# BinaryWatch_v0_5.net
KiCad netlist of a schematic drawn in EAGLE
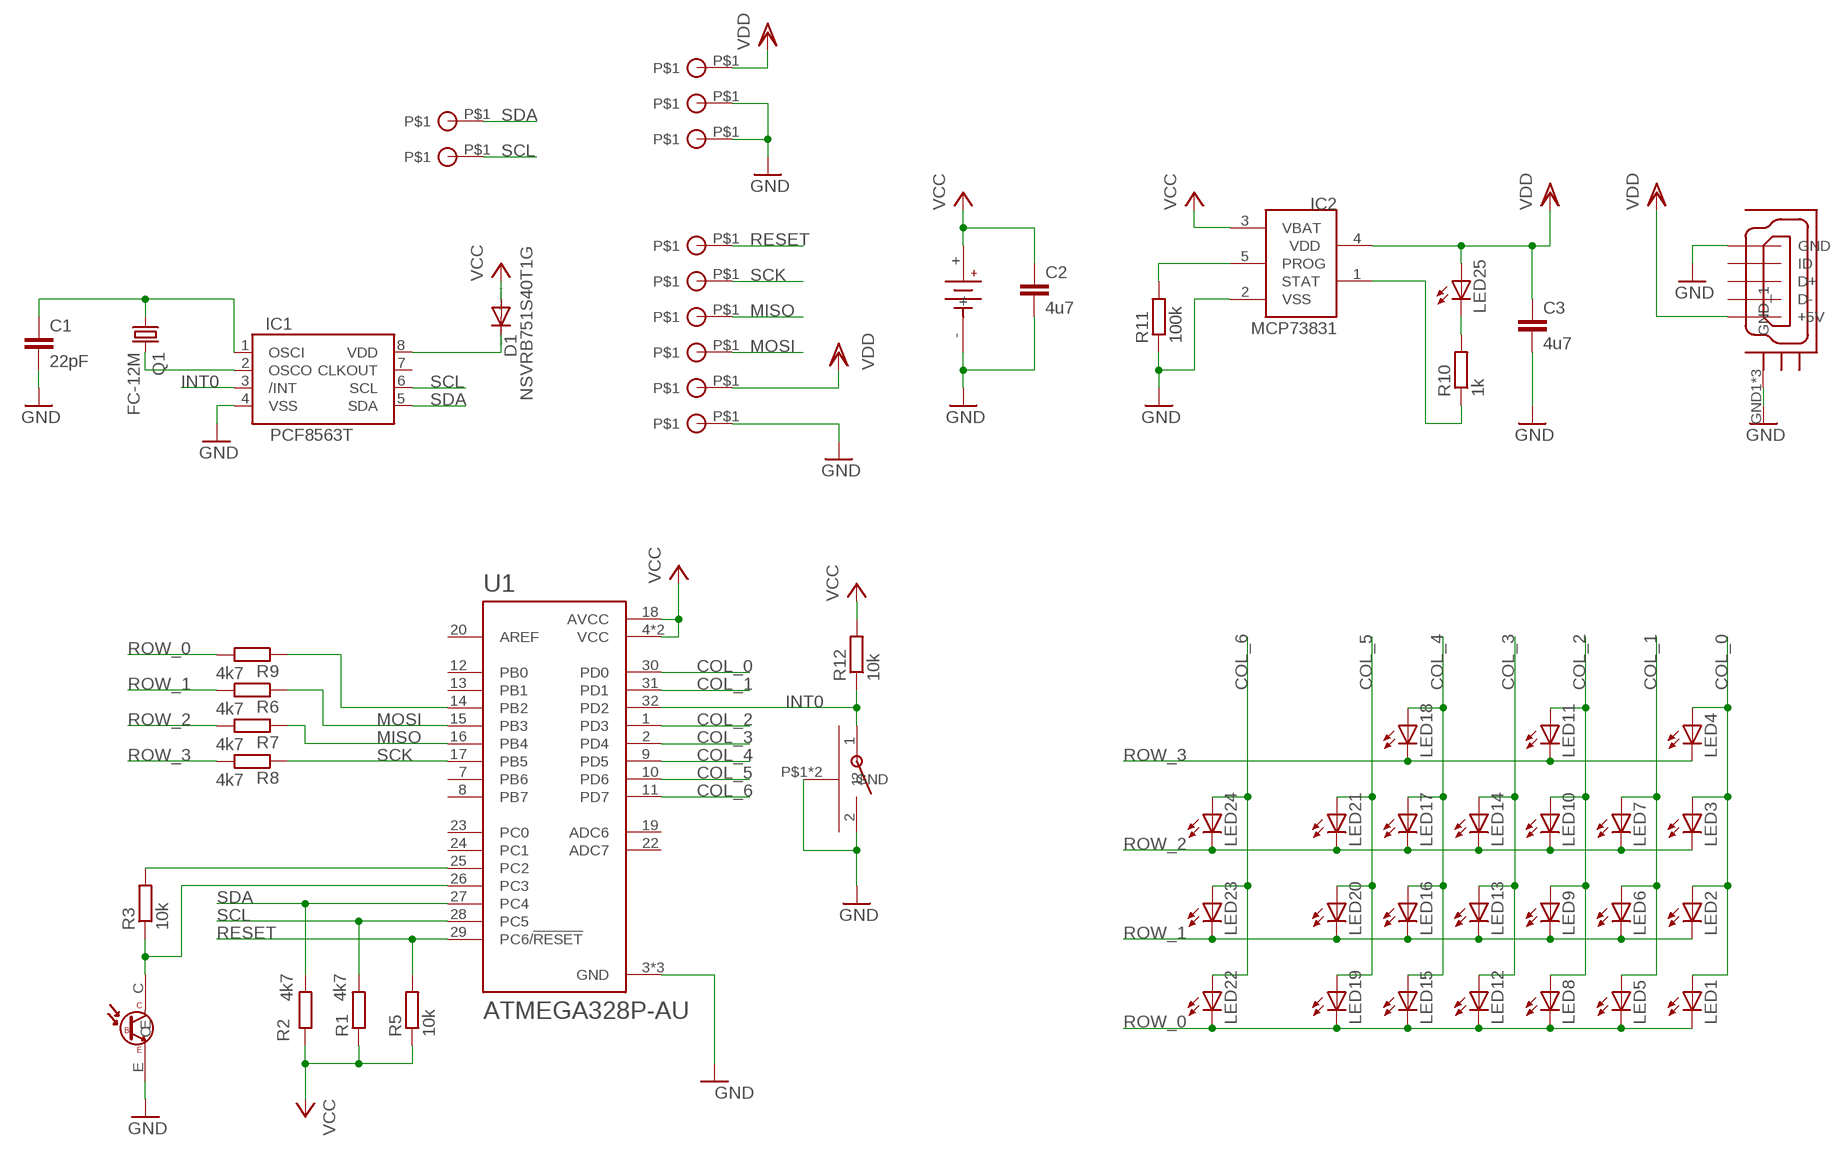
[diagram p0: schematic, sheet 1]

(export (version "E")
  (design (tool "Eeschema 10.0.6"))
  (components
    (comp (ref "C1")
      (value "22pF")
      (footprint "eagle-import:C0603")
      (libsource (lib "eagle-import") (part "C-EUC0603"))
    )
    (comp (ref "C2")
      (value "4u7")
      (footprint "eagle-import:C0603")
      (libsource (lib "eagle-import") (part "C-EUC0603"))
    )
    (comp (ref "C3")
      (value "4u7")
      (footprint "eagle-import:C0603")
      (libsource (lib "eagle-import") (part "C-EUC0603"))
    )
    (comp (ref "D1")
      (value "NSVRB751S40T1G")
      (footprint "eagle-import:SOD523")
      (libsource (lib "eagle-import") (part "DIODE-SOD523"))
    )
    (comp (ref "IC1")
      (value "PCF8563T")
      (footprint "eagle-import:SO8")
      (libsource (lib "eagle-import") (part "PCF8563T"))
    )
    (comp (ref "IC2")
      (value "MCP73831")
      (footprint "eagle-import:SOT23-5L")
      (libsource (lib "eagle-import") (part "MCP73831"))
    )
    (comp (ref "LED1")
      (value "LEDSML0603")
      (footprint "eagle-import:SML0603")
      (libsource (lib "eagle-import") (part "LEDSML0603"))
    )
    (comp (ref "LED2")
      (value "LEDSML0603")
      (footprint "eagle-import:SML0603")
      (libsource (lib "eagle-import") (part "LEDSML0603"))
    )
    (comp (ref "LED3")
      (value "LEDSML0603")
      (footprint "eagle-import:SML0603")
      (libsource (lib "eagle-import") (part "LEDSML0603"))
    )
    (comp (ref "LED4")
      (value "LEDSML0603")
      (footprint "eagle-import:SML0603")
      (libsource (lib "eagle-import") (part "LEDSML0603"))
    )
    (comp (ref "LED5")
      (value "LEDSML0603")
      (footprint "eagle-import:SML0603")
      (libsource (lib "eagle-import") (part "LEDSML0603"))
    )
    (comp (ref "LED6")
      (value "LEDSML0603")
      (footprint "eagle-import:SML0603")
      (libsource (lib "eagle-import") (part "LEDSML0603"))
    )
    (comp (ref "LED7")
      (value "LEDSML0603")
      (footprint "eagle-import:SML0603")
      (libsource (lib "eagle-import") (part "LEDSML0603"))
    )
    (comp (ref "LED8")
      (value "LEDSML0603")
      (footprint "eagle-import:SML0603")
      (libsource (lib "eagle-import") (part "LEDSML0603"))
    )
    (comp (ref "LED9")
      (value "LEDSML0603")
      (footprint "eagle-import:SML0603")
      (libsource (lib "eagle-import") (part "LEDSML0603"))
    )
    (comp (ref "LED10")
      (value "LEDSML0603")
      (footprint "eagle-import:SML0603")
      (libsource (lib "eagle-import") (part "LEDSML0603"))
    )
    (comp (ref "LED11")
      (value "LEDSML0603")
      (footprint "eagle-import:SML0603")
      (libsource (lib "eagle-import") (part "LEDSML0603"))
    )
    (comp (ref "LED12")
      (value "LEDSML0603")
      (footprint "eagle-import:SML0603")
      (libsource (lib "eagle-import") (part "LEDSML0603"))
    )
    (comp (ref "LED13")
      (value "LEDSML0603")
      (footprint "eagle-import:SML0603")
      (libsource (lib "eagle-import") (part "LEDSML0603"))
    )
    (comp (ref "LED14")
      (value "LEDSML0603")
      (footprint "eagle-import:SML0603")
      (libsource (lib "eagle-import") (part "LEDSML0603"))
    )
    (comp (ref "LED15")
      (value "LEDSML0603")
      (footprint "eagle-import:SML0603")
      (libsource (lib "eagle-import") (part "LEDSML0603"))
    )
    (comp (ref "LED16")
      (value "LEDSML0603")
      (footprint "eagle-import:SML0603")
      (libsource (lib "eagle-import") (part "LEDSML0603"))
    )
    (comp (ref "LED17")
      (value "LEDSML0603")
      (footprint "eagle-import:SML0603")
      (libsource (lib "eagle-import") (part "LEDSML0603"))
    )
    (comp (ref "LED18")
      (value "LEDSML0603")
      (footprint "eagle-import:SML0603")
      (libsource (lib "eagle-import") (part "LEDSML0603"))
    )
    (comp (ref "LED19")
      (value "LEDSML0603")
      (footprint "eagle-import:SML0603")
      (libsource (lib "eagle-import") (part "LEDSML0603"))
    )
    (comp (ref "LED20")
      (value "LEDSML0603")
      (footprint "eagle-import:SML0603")
      (libsource (lib "eagle-import") (part "LEDSML0603"))
    )
    (comp (ref "LED21")
      (value "LEDSML0603")
      (footprint "eagle-import:SML0603")
      (libsource (lib "eagle-import") (part "LEDSML0603"))
    )
    (comp (ref "LED22")
      (value "LEDSML0603")
      (footprint "eagle-import:SML0603")
      (libsource (lib "eagle-import") (part "LEDSML0603"))
    )
    (comp (ref "LED23")
      (value "LEDSML0603")
      (footprint "eagle-import:SML0603")
      (libsource (lib "eagle-import") (part "LEDSML0603"))
    )
    (comp (ref "LED24")
      (value "LEDSML0603")
      (footprint "eagle-import:SML0603")
      (libsource (lib "eagle-import") (part "LEDSML0603"))
    )
    (comp (ref "LED25")
      (value "LEDSML0603")
      (footprint "eagle-import:SML0603")
      (libsource (lib "eagle-import") (part "LEDSML0603"))
    )
    (comp (ref "Q1")
      (value "FC-12M")
      (footprint "eagle-import:FC-12M")
      (libsource (lib "eagle-import") (part "FC-12M"))
    )
    (comp (ref "R1")
      (value "4k7")
      (footprint "eagle-import:R0603")
      (libsource (lib "eagle-import") (part "resistor_R-EU_R0603"))
    )
    (comp (ref "R2")
      (value "4k7")
      (footprint "eagle-import:R0603")
      (libsource (lib "eagle-import") (part "resistor_R-EU_R0603"))
    )
    (comp (ref "R3")
      (value "10k")
      (footprint "eagle-import:R0603")
      (libsource (lib "eagle-import") (part "R-EU_R0603"))
    )
    (comp (ref "R5")
      (value "10k")
      (footprint "eagle-import:R0603")
      (libsource (lib "eagle-import") (part "resistor_R-EU_R0603"))
    )
    (comp (ref "R6")
      (value "4k7")
      (footprint "eagle-import:R0603")
      (libsource (lib "eagle-import") (part "resistor_R-EU_R0603"))
    )
    (comp (ref "R7")
      (value "4k7")
      (footprint "eagle-import:R0603")
      (libsource (lib "eagle-import") (part "resistor_R-EU_R0603"))
    )
    (comp (ref "R8")
      (value "4k7")
      (footprint "eagle-import:R0603")
      (libsource (lib "eagle-import") (part "resistor_R-EU_R0603"))
    )
    (comp (ref "R9")
      (value "4k7")
      (footprint "eagle-import:R0603")
      (libsource (lib "eagle-import") (part "resistor_R-EU_R0603"))
    )
    (comp (ref "R10")
      (value "1k")
      (footprint "eagle-import:R0603")
      (libsource (lib "eagle-import") (part "R-EU_R0603"))
    )
    (comp (ref "R11")
      (value "100k")
      (footprint "eagle-import:R0603")
      (libsource (lib "eagle-import") (part "R-EU_R0603"))
    )
    (comp (ref "R12")
      (value "10k")
      (footprint "eagle-import:R0603")
      (libsource (lib "eagle-import") (part "rcl_334_R-EU_R0603"))
    )
    (comp (ref "U$1")
      (value "2032")
      (footprint "eagle-import:2032_45DEG")
      (libsource (lib "eagle-import") (part "2032"))
    )
    (comp (ref "U$2")
      (value "CONTACT_1_8MM")
      (footprint "eagle-import:CONTACT_1_8MM")
      (libsource (lib "eagle-import") (part "CONTACT_1_8MM"))
    )
    (comp (ref "U$3")
      (value "CONTACT_1_8MM")
      (footprint "eagle-import:CONTACT_1_8MM")
      (libsource (lib "eagle-import") (part "CONTACT_1_8MM"))
    )
    (comp (ref "U$4")
      (value "CONTACT_1_8MM")
      (footprint "eagle-import:CONTACT_1_8MM")
      (libsource (lib "eagle-import") (part "CONTACT_1_8MM"))
    )
    (comp (ref "U$5")
      (value "CONTACT_1_8MM")
      (footprint "eagle-import:CONTACT_1_8MM")
      (libsource (lib "eagle-import") (part "CONTACT_1_8MM"))
    )
    (comp (ref "U$6")
      (value "CONTACT_1_8MM")
      (footprint "eagle-import:CONTACT_1_8MM")
      (libsource (lib "eagle-import") (part "CONTACT_1_8MM"))
    )
    (comp (ref "U$7")
      (value "CONTACT_1_8MM")
      (footprint "eagle-import:CONTACT_1_8MM")
      (libsource (lib "eagle-import") (part "CONTACT_1_8MM"))
    )
    (comp (ref "U$8")
      (value "TACK_SWITCH")
      (footprint "eagle-import:TL3330")
      (libsource (lib "eagle-import") (part "TACK_SWITCH"))
    )
    (comp (ref "U$9")
      (value "CONTACT_1_8MM")
      (footprint "eagle-import:CONTACT_1_8MM")
      (libsource (lib "eagle-import") (part "CONTACT_1_8MM"))
    )
    (comp (ref "U$10")
      (value "MICRO_USB_VERTICAL")
      (footprint "eagle-import:MICRO_USB_VERTICAL")
      (libsource (lib "eagle-import") (part "MICRO_USB_VERTICAL"))
    )
    (comp (ref "U$11")
      (value "CONTACT_1_8MM")
      (footprint "eagle-import:CONTACT_1_8MM")
      (libsource (lib "eagle-import") (part "CONTACT_1_8MM"))
    )
    (comp (ref "U$12")
      (value "CONTACT_1_8MM")
      (footprint "eagle-import:CONTACT_1_8MM")
      (libsource (lib "eagle-import") (part "CONTACT_1_8MM"))
    )
    (comp (ref "U$13")
      (value "CONTACT_1_8MM")
      (footprint "eagle-import:CONTACT_1_8MM")
      (libsource (lib "eagle-import") (part "CONTACT_1_8MM"))
    )
    (comp (ref "U$14")
      (value "CONTACT_1_8MM")
      (footprint "eagle-import:CONTACT_1_8MM")
      (libsource (lib "eagle-import") (part "CONTACT_1_8MM"))
    )
    (comp (ref "U$15")
      (value "PHOTOTRANSISTOR_0603")
      (footprint "eagle-import:PHOTO_TRANS_0603")
      (libsource (lib "eagle-import") (part "PHOTOTRANSISTOR_0603"))
    )
    (comp (ref "U1")
      (value "ATMEGA328P-AU")
      (footprint "eagle-import:QFP80P900X900X120-32N")
      (fields (field (name "MF") "Microchip"))
      (libsource (lib "eagle-import") (part "ATMEGA328P-AU"))
    )
  )
  (nets
    (net (code "1") (name "/COL_0") (class "Default")
      (node (ref "LED1") (pin "A") (pinfunction "A_A") (pintype "passive"))
      (node (ref "LED2") (pin "A") (pinfunction "A_A") (pintype "passive"))
      (node (ref "LED3") (pin "A") (pinfunction "A_A") (pintype "passive"))
      (node (ref "LED4") (pin "A") (pinfunction "A_A") (pintype "passive"))
      (node (ref "U1") (pin "30") (pinfunction "PD0_30") (pintype "bidirectional"))
    )
    (net (code "2") (name "/COL_1") (class "Default")
      (node (ref "LED5") (pin "A") (pinfunction "A_A") (pintype "passive"))
      (node (ref "LED6") (pin "A") (pinfunction "A_A") (pintype "passive"))
      (node (ref "LED7") (pin "A") (pinfunction "A_A") (pintype "passive"))
      (node (ref "U1") (pin "31") (pinfunction "PD1_31") (pintype "bidirectional"))
    )
    (net (code "3") (name "/COL_2") (class "Default")
      (node (ref "LED10") (pin "A") (pinfunction "A_A") (pintype "passive"))
      (node (ref "LED11") (pin "A") (pinfunction "A_A") (pintype "passive"))
      (node (ref "LED8") (pin "A") (pinfunction "A_A") (pintype "passive"))
      (node (ref "LED9") (pin "A") (pinfunction "A_A") (pintype "passive"))
      (node (ref "U1") (pin "1") (pinfunction "PD3_1") (pintype "bidirectional"))
    )
    (net (code "4") (name "/COL_3") (class "Default")
      (node (ref "LED12") (pin "A") (pinfunction "A_A") (pintype "passive"))
      (node (ref "LED13") (pin "A") (pinfunction "A_A") (pintype "passive"))
      (node (ref "LED14") (pin "A") (pinfunction "A_A") (pintype "passive"))
      (node (ref "U1") (pin "2") (pinfunction "PD4_2") (pintype "bidirectional"))
    )
    (net (code "5") (name "/COL_4") (class "Default")
      (node (ref "LED15") (pin "A") (pinfunction "A_A") (pintype "passive"))
      (node (ref "LED16") (pin "A") (pinfunction "A_A") (pintype "passive"))
      (node (ref "LED17") (pin "A") (pinfunction "A_A") (pintype "passive"))
      (node (ref "LED18") (pin "A") (pinfunction "A_A") (pintype "passive"))
      (node (ref "U1") (pin "9") (pinfunction "PD5_9") (pintype "bidirectional"))
    )
    (net (code "6") (name "/COL_5") (class "Default")
      (node (ref "LED19") (pin "A") (pinfunction "A_A") (pintype "passive"))
      (node (ref "LED20") (pin "A") (pinfunction "A_A") (pintype "passive"))
      (node (ref "LED21") (pin "A") (pinfunction "A_A") (pintype "passive"))
      (node (ref "U1") (pin "10") (pinfunction "PD6_10") (pintype "bidirectional"))
    )
    (net (code "7") (name "/COL_6") (class "Default")
      (node (ref "LED22") (pin "A") (pinfunction "A_A") (pintype "passive"))
      (node (ref "LED23") (pin "A") (pinfunction "A_A") (pintype "passive"))
      (node (ref "LED24") (pin "A") (pinfunction "A_A") (pintype "passive"))
      (node (ref "U1") (pin "11") (pinfunction "PD7_11") (pintype "bidirectional"))
    )
    (net (code "8") (name "/INT0") (class "Default")
      (node (ref "IC1") (pin "3") (pinfunction "/INT_3") (pintype "bidirectional"))
      (node (ref "R12") (pin "1") (pinfunction "1_1") (pintype "passive"))
      (node (ref "U$8") (pin "1") (pinfunction "1_1") (pintype "bidirectional"))
      (node (ref "U1") (pin "32") (pinfunction "PD2_32") (pintype "bidirectional"))
    )
    (net (code "9") (name "/MISO") (class "Default")
      (node (ref "R7") (pin "1") (pinfunction "1_1") (pintype "passive"))
      (node (ref "U$5") (pin "P$1") (pinfunction "P$1_P$1") (pintype "bidirectional"))
      (node (ref "U1") (pin "16") (pinfunction "PB4_16") (pintype "bidirectional"))
    )
    (net (code "10") (name "/MOSI") (class "Default")
      (node (ref "R6") (pin "1") (pinfunction "1_1") (pintype "passive"))
      (node (ref "U$4") (pin "P$1") (pinfunction "P$1_P$1") (pintype "bidirectional"))
      (node (ref "U1") (pin "15") (pinfunction "PB3_15") (pintype "bidirectional"))
    )
    (net (code "11") (name "/RESET") (class "Default")
      (node (ref "R5") (pin "2") (pinfunction "2_2") (pintype "passive"))
      (node (ref "U$7") (pin "P$1") (pinfunction "P$1_P$1") (pintype "bidirectional"))
      (node (ref "U1") (pin "29") (pinfunction "PC6/~{RESET}_29") (pintype "bidirectional"))
    )
    (net (code "12") (name "/ROW_0") (class "Default")
      (node (ref "LED1") (pin "C") (pinfunction "C_C") (pintype "passive"))
      (node (ref "LED12") (pin "C") (pinfunction "C_C") (pintype "passive"))
      (node (ref "LED15") (pin "C") (pinfunction "C_C") (pintype "passive"))
      (node (ref "LED19") (pin "C") (pinfunction "C_C") (pintype "passive"))
      (node (ref "LED22") (pin "C") (pinfunction "C_C") (pintype "passive"))
      (node (ref "LED5") (pin "C") (pinfunction "C_C") (pintype "passive"))
      (node (ref "LED8") (pin "C") (pinfunction "C_C") (pintype "passive"))
      (node (ref "R9") (pin "2") (pinfunction "2_2") (pintype "passive"))
    )
    (net (code "13") (name "/ROW_1") (class "Default")
      (node (ref "LED13") (pin "C") (pinfunction "C_C") (pintype "passive"))
      (node (ref "LED16") (pin "C") (pinfunction "C_C") (pintype "passive"))
      (node (ref "LED2") (pin "C") (pinfunction "C_C") (pintype "passive"))
      (node (ref "LED20") (pin "C") (pinfunction "C_C") (pintype "passive"))
      (node (ref "LED23") (pin "C") (pinfunction "C_C") (pintype "passive"))
      (node (ref "LED6") (pin "C") (pinfunction "C_C") (pintype "passive"))
      (node (ref "LED9") (pin "C") (pinfunction "C_C") (pintype "passive"))
      (node (ref "R6") (pin "2") (pinfunction "2_2") (pintype "passive"))
    )
    (net (code "14") (name "/ROW_2") (class "Default")
      (node (ref "LED10") (pin "C") (pinfunction "C_C") (pintype "passive"))
      (node (ref "LED14") (pin "C") (pinfunction "C_C") (pintype "passive"))
      (node (ref "LED17") (pin "C") (pinfunction "C_C") (pintype "passive"))
      (node (ref "LED21") (pin "C") (pinfunction "C_C") (pintype "passive"))
      (node (ref "LED24") (pin "C") (pinfunction "C_C") (pintype "passive"))
      (node (ref "LED3") (pin "C") (pinfunction "C_C") (pintype "passive"))
      (node (ref "LED7") (pin "C") (pinfunction "C_C") (pintype "passive"))
      (node (ref "R7") (pin "2") (pinfunction "2_2") (pintype "passive"))
    )
    (net (code "15") (name "/ROW_3") (class "Default")
      (node (ref "LED11") (pin "C") (pinfunction "C_C") (pintype "passive"))
      (node (ref "LED18") (pin "C") (pinfunction "C_C") (pintype "passive"))
      (node (ref "LED4") (pin "C") (pinfunction "C_C") (pintype "passive"))
      (node (ref "R8") (pin "2") (pinfunction "2_2") (pintype "passive"))
    )
    (net (code "16") (name "/SCK") (class "Default")
      (node (ref "R8") (pin "1") (pinfunction "1_1") (pintype "passive"))
      (node (ref "U$6") (pin "P$1") (pinfunction "P$1_P$1") (pintype "bidirectional"))
      (node (ref "U1") (pin "17") (pinfunction "PB5_17") (pintype "bidirectional"))
    )
    (net (code "17") (name "/SCL") (class "Default")
      (node (ref "IC1") (pin "6") (pinfunction "SCL_6") (pintype "bidirectional"))
      (node (ref "R1") (pin "2") (pinfunction "2_2") (pintype "passive"))
      (node (ref "U$14") (pin "P$1") (pinfunction "P$1_P$1") (pintype "bidirectional"))
      (node (ref "U1") (pin "28") (pinfunction "PC5_28") (pintype "bidirectional"))
    )
    (net (code "18") (name "/SDA") (class "Default")
      (node (ref "IC1") (pin "5") (pinfunction "SDA_5") (pintype "bidirectional"))
      (node (ref "R2") (pin "2") (pinfunction "2_2") (pintype "passive"))
      (node (ref "U$13") (pin "P$1") (pinfunction "P$1_P$1") (pintype "bidirectional"))
      (node (ref "U1") (pin "27") (pinfunction "PC4_27") (pintype "bidirectional"))
    )
    (net (code "19") (name "GND") (class "Default")
      (node (ref "C1") (pin "2") (pinfunction "2_2") (pintype "passive"))
      (node (ref "C2") (pin "2") (pinfunction "2_2") (pintype "passive"))
      (node (ref "C3") (pin "2") (pinfunction "2_2") (pintype "passive"))
      (node (ref "IC1") (pin "4") (pinfunction "VSS_4") (pintype "bidirectional"))
      (node (ref "IC2") (pin "2") (pinfunction "VSS_2") (pintype "bidirectional"))
      (node (ref "R11") (pin "1") (pinfunction "1_1") (pintype "passive"))
      (node (ref "U$1") (pin "-") (pinfunction "-_-") (pintype "bidirectional"))
      (node (ref "U$10") (pin "5") (pinfunction "GND_5") (pintype "passive"))
      (node (ref "U$10") (pin "GND1") (pinfunction "GND_1_GND1") (pintype "bidirectional"))
      (node (ref "U$10") (pin "GND2") (pinfunction "GND_1_GND2") (pintype "bidirectional"))
      (node (ref "U$10") (pin "GND3") (pinfunction "GND_1_GND3") (pintype "bidirectional"))
      (node (ref "U$12") (pin "P$1") (pinfunction "P$1_P$1") (pintype "bidirectional"))
      (node (ref "U$15") (pin "E") (pinfunction "E_E") (pintype "bidirectional"))
      (node (ref "U$2") (pin "P$1") (pinfunction "P$1_P$1") (pintype "bidirectional"))
      (node (ref "U$8") (pin "2") (pinfunction "2_2") (pintype "bidirectional"))
      (node (ref "U$8") (pin "P$1") (pinfunction "GND_P$1") (pintype "bidirectional"))
      (node (ref "U$8") (pin "P$2") (pinfunction "GND_P$2") (pintype "bidirectional"))
      (node (ref "U$9") (pin "P$1") (pinfunction "P$1_P$1") (pintype "bidirectional"))
      (node (ref "U1") (pin "21") (pinfunction "GND_21") (pintype "power_in"))
      (node (ref "U1") (pin "3") (pinfunction "GND_3") (pintype "power_in"))
      (node (ref "U1") (pin "5") (pinfunction "GND_5") (pintype "power_in"))
    )
    (net (code "20") (name "Net-(IC1-OSCI)") (class "Default")
      (node (ref "C1") (pin "1") (pinfunction "1_1") (pintype "passive"))
      (node (ref "IC1") (pin "1") (pinfunction "OSCI_1") (pintype "bidirectional"))
      (node (ref "Q1") (pin "1") (pinfunction "1_1") (pintype "passive"))
    )
    (net (code "21") (name "Net-(IC1-OSCO)") (class "Default")
      (node (ref "IC1") (pin "2") (pinfunction "OSCO_2") (pintype "bidirectional"))
      (node (ref "Q1") (pin "2") (pinfunction "2_2") (pintype "passive"))
    )
    (net (code "22") (name "Net-(IC1-VDD)") (class "Default")
      (node (ref "D1") (pin "C") (pinfunction "C_C") (pintype "passive"))
      (node (ref "IC1") (pin "8") (pinfunction "VDD_8") (pintype "bidirectional"))
    )
    (net (code "23") (name "Net-(IC2-PROG)") (class "Default")
      (node (ref "IC2") (pin "5") (pinfunction "PROG_5") (pintype "bidirectional"))
      (node (ref "R11") (pin "2") (pinfunction "2_2") (pintype "passive"))
    )
    (net (code "24") (name "Net-(IC2-STAT)") (class "Default")
      (node (ref "IC2") (pin "1") (pinfunction "STAT_1") (pintype "bidirectional"))
      (node (ref "R10") (pin "1") (pinfunction "1_1") (pintype "passive"))
    )
    (net (code "25") (name "Net-(LED25-PadC)") (class "Default")
      (node (ref "LED25") (pin "C") (pinfunction "C_C") (pintype "passive"))
      (node (ref "R10") (pin "2") (pinfunction "2_2") (pintype "passive"))
    )
    (net (code "26") (name "Net-(U1-PB2)") (class "Default")
      (node (ref "R9") (pin "1") (pinfunction "1_1") (pintype "passive"))
      (node (ref "U1") (pin "14") (pinfunction "PB2_14") (pintype "bidirectional"))
    )
    (net (code "27") (name "Net-(U1-PC2)") (class "Default")
      (node (ref "R3") (pin "2") (pinfunction "2_2") (pintype "passive"))
      (node (ref "U1") (pin "25") (pinfunction "PC2_25") (pintype "bidirectional"))
    )
    (net (code "28") (name "Net-(U1-PC3)") (class "Default")
      (node (ref "R3") (pin "1") (pinfunction "1_1") (pintype "passive"))
      (node (ref "U$15") (pin "C") (pinfunction "C_C") (pintype "bidirectional"))
      (node (ref "U1") (pin "26") (pinfunction "PC3_26") (pintype "bidirectional"))
    )
    (net (code "29") (name "VCC") (class "Default")
      (node (ref "C2") (pin "1") (pinfunction "1_1") (pintype "passive"))
      (node (ref "D1") (pin "A") (pinfunction "A_A") (pintype "passive"))
      (node (ref "IC2") (pin "3") (pinfunction "VBAT_3") (pintype "bidirectional"))
      (node (ref "R1") (pin "1") (pinfunction "1_1") (pintype "passive"))
      (node (ref "R12") (pin "2") (pinfunction "2_2") (pintype "passive"))
      (node (ref "R2") (pin "1") (pinfunction "1_1") (pintype "passive"))
      (node (ref "R5") (pin "1") (pinfunction "1_1") (pintype "passive"))
      (node (ref "U$1") (pin "+") (pinfunction "+_+") (pintype "bidirectional"))
      (node (ref "U1") (pin "18") (pinfunction "AVCC_18") (pintype "power_in"))
      (node (ref "U1") (pin "4") (pinfunction "VCC_4") (pintype "power_in"))
      (node (ref "U1") (pin "6") (pinfunction "VCC_6") (pintype "power_in"))
    )
    (net (code "30") (name "VDD") (class "Default")
      (node (ref "C3") (pin "1") (pinfunction "1_1") (pintype "passive"))
      (node (ref "IC2") (pin "4") (pinfunction "VDD_4") (pintype "bidirectional"))
      (node (ref "LED25") (pin "A") (pinfunction "A_A") (pintype "passive"))
      (node (ref "U$10") (pin "1") (pinfunction "+5V_1") (pintype "passive"))
      (node (ref "U$11") (pin "P$1") (pinfunction "P$1_P$1") (pintype "bidirectional"))
      (node (ref "U$3") (pin "P$1") (pinfunction "P$1_P$1") (pintype "bidirectional"))
    )
    (net (code "31") (name "unconnected-(IC1-CLKOUT-Pad7)") (class "Default")
      (node (ref "IC1") (pin "7") (pinfunction "CLKOUT_7") (pintype "bidirectional"))
    )
    (net (code "32") (name "unconnected-(U$10-D+-Pad3)") (class "Default")
      (node (ref "U$10") (pin "3") (pinfunction "D+_3") (pintype "passive"))
    )
    (net (code "33") (name "unconnected-(U$10-D--Pad2)") (class "Default")
      (node (ref "U$10") (pin "2") (pinfunction "D-_2") (pintype "passive"))
    )
    (net (code "34") (name "unconnected-(U$10-ID-Pad4)") (class "Default")
      (node (ref "U$10") (pin "4") (pinfunction "ID_4") (pintype "passive"))
    )
    (net (code "35") (name "unconnected-(U1-ADC6-Pad19)") (class "Default")
      (node (ref "U1") (pin "19") (pinfunction "ADC6_19") (pintype "bidirectional"))
    )
    (net (code "36") (name "unconnected-(U1-ADC7-Pad22)") (class "Default")
      (node (ref "U1") (pin "22") (pinfunction "ADC7_22") (pintype "bidirectional"))
    )
    (net (code "37") (name "unconnected-(U1-AREF-Pad20)") (class "Default")
      (node (ref "U1") (pin "20") (pinfunction "AREF_20") (pintype "input"))
    )
    (net (code "38") (name "unconnected-(U1-PB0-Pad12)") (class "Default")
      (node (ref "U1") (pin "12") (pinfunction "PB0_12") (pintype "bidirectional"))
    )
    (net (code "39") (name "unconnected-(U1-PB1-Pad13)") (class "Default")
      (node (ref "U1") (pin "13") (pinfunction "PB1_13") (pintype "bidirectional"))
    )
    (net (code "40") (name "unconnected-(U1-PB6-Pad7)") (class "Default")
      (node (ref "U1") (pin "7") (pinfunction "PB6_7") (pintype "bidirectional"))
    )
    (net (code "41") (name "unconnected-(U1-PB7-Pad8)") (class "Default")
      (node (ref "U1") (pin "8") (pinfunction "PB7_8") (pintype "bidirectional"))
    )
    (net (code "42") (name "unconnected-(U1-PC0-Pad23)") (class "Default")
      (node (ref "U1") (pin "23") (pinfunction "PC0_23") (pintype "bidirectional"))
    )
    (net (code "43") (name "unconnected-(U1-PC1-Pad24)") (class "Default")
      (node (ref "U1") (pin "24") (pinfunction "PC1_24") (pintype "bidirectional"))
    )
  )
)
